# ws2812_clock.net
KiCad netlist of a schematic drawn in EAGLE
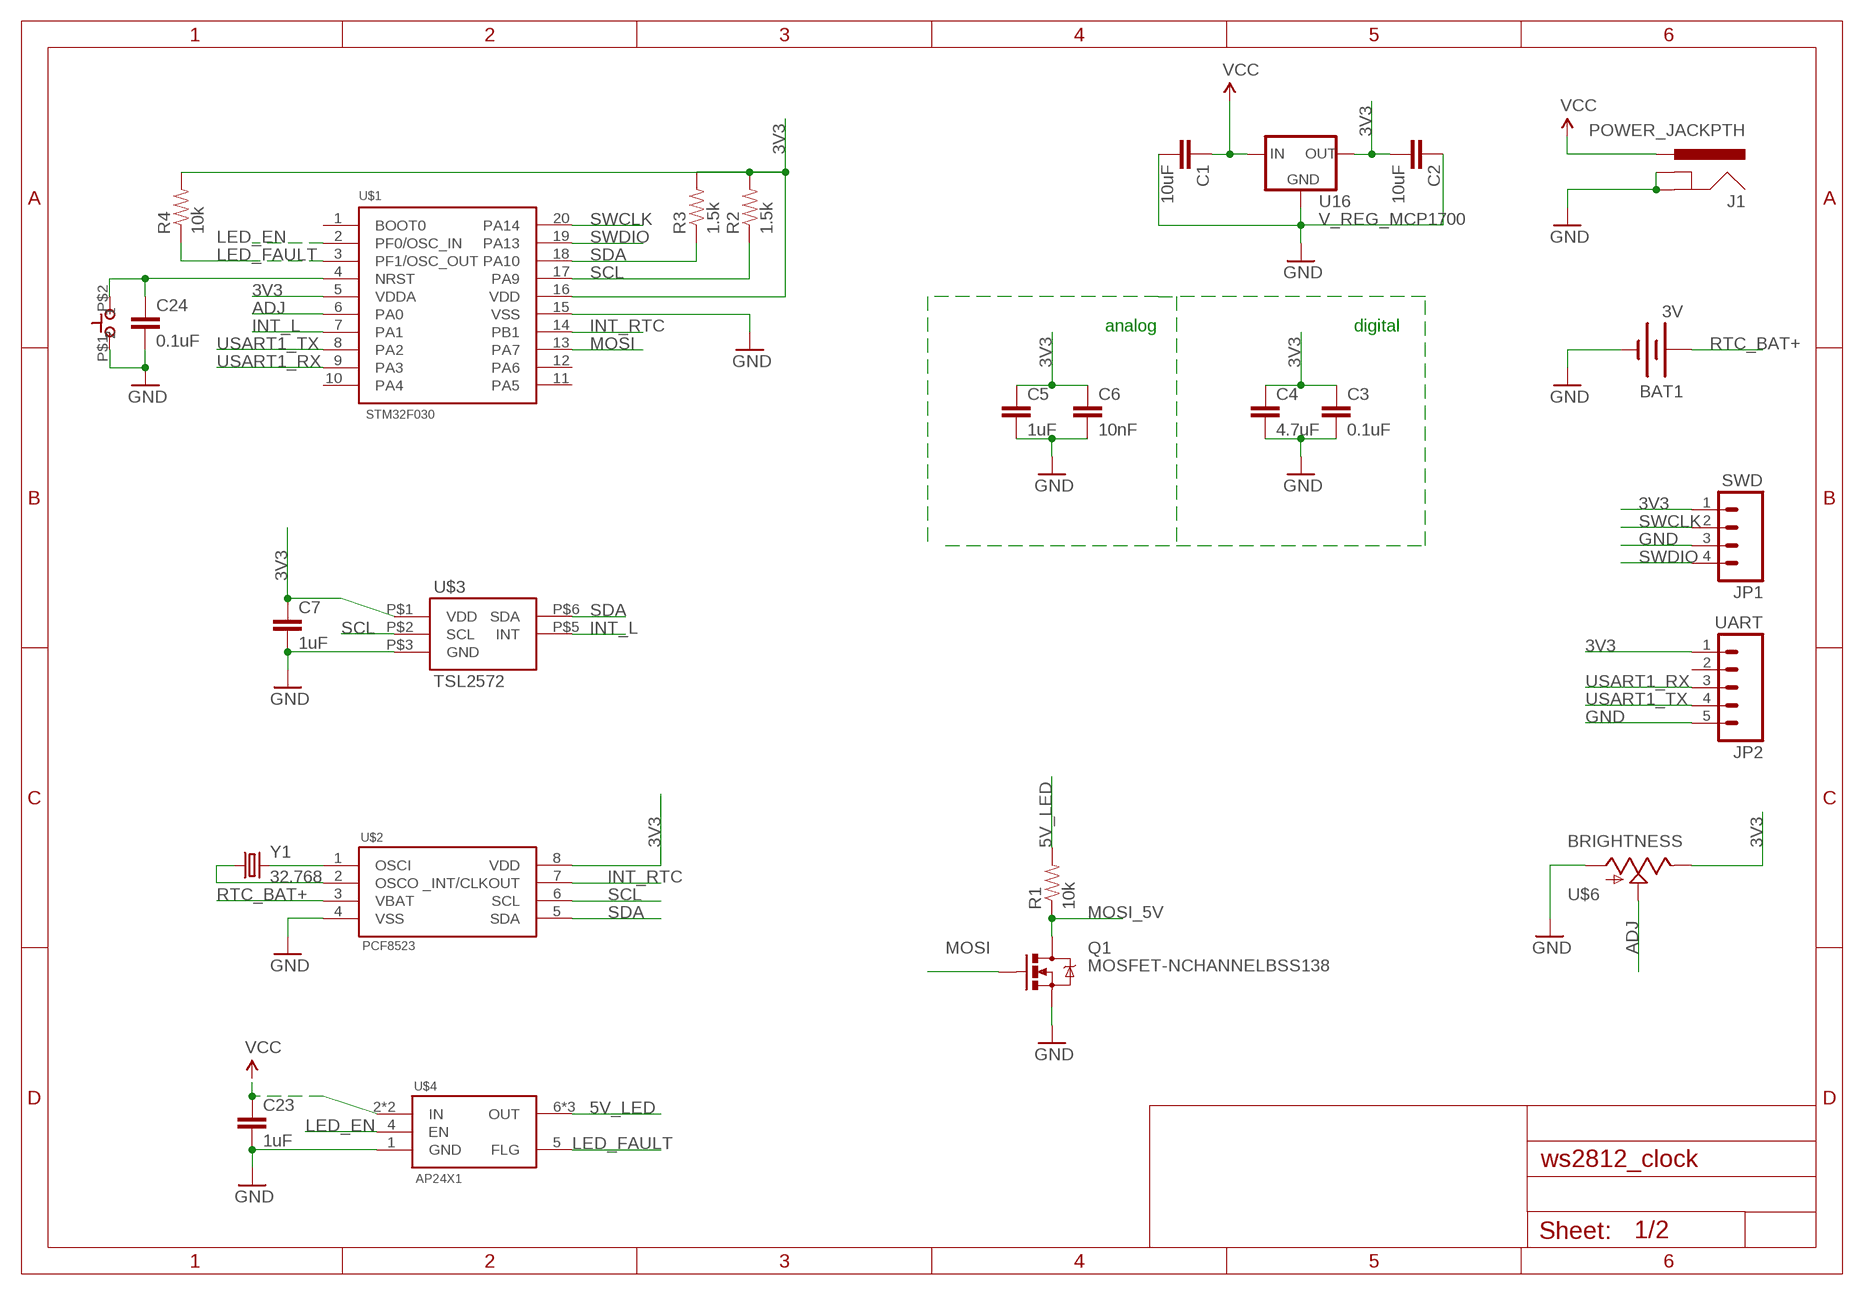
[diagram p0: schematic, sheet 1]
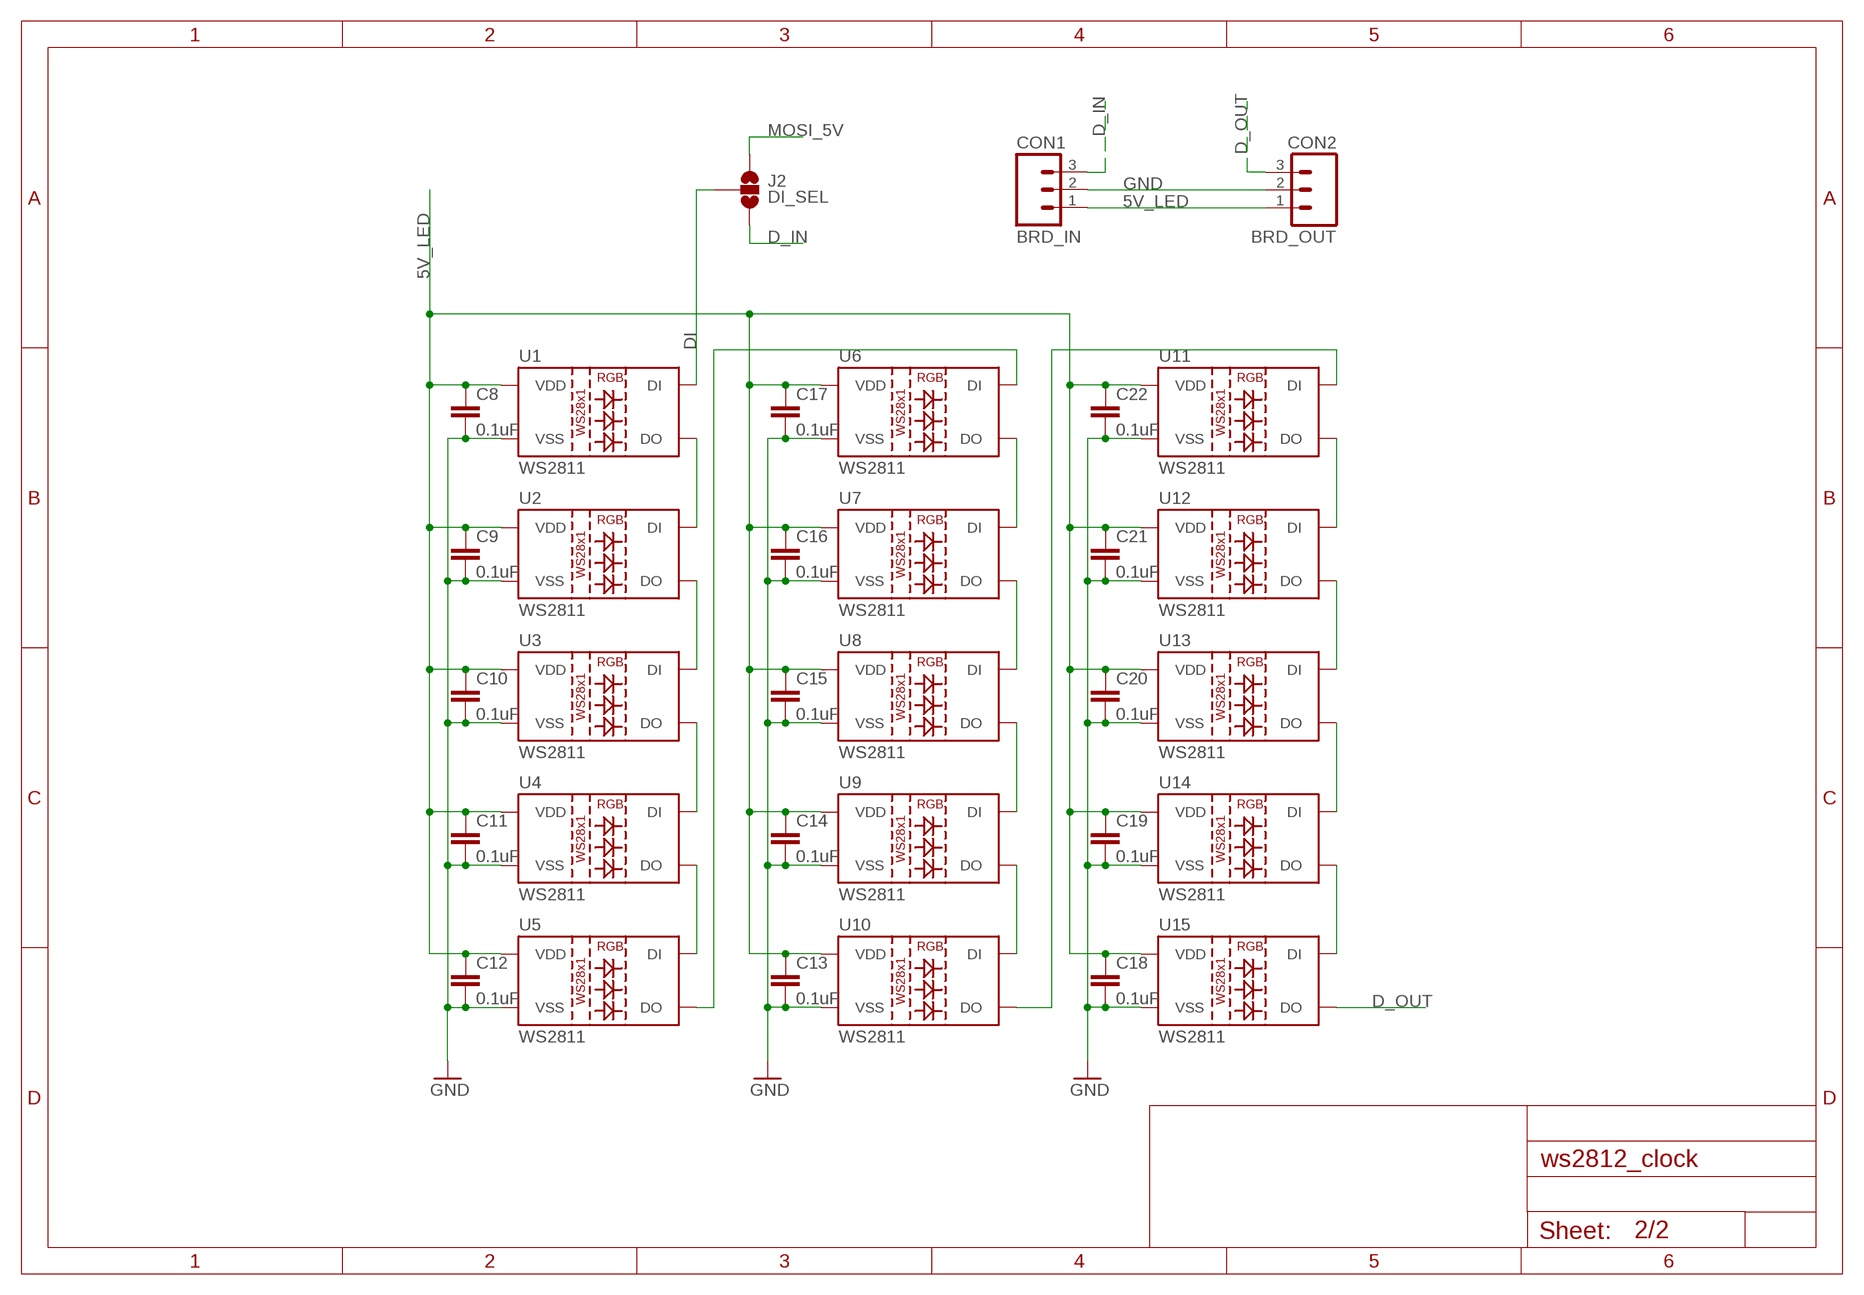
[diagram p1: schematic, sheet 2]

(export (version "E")
  (design (tool "Eeschema 10.0.6"))
  (components
    (comp (ref "C8")
      (value "0.1uF")
      (footprint "eagle-import:0603-CAP")
      (libsource (lib "eagle-import") (part "CAP0603-CAP"))
    )
    (comp (ref "C9")
      (value "0.1uF")
      (footprint "eagle-import:0603-CAP")
      (libsource (lib "eagle-import") (part "CAP0603-CAP"))
    )
    (comp (ref "C10")
      (value "0.1uF")
      (footprint "eagle-import:0603-CAP")
      (libsource (lib "eagle-import") (part "CAP0603-CAP"))
    )
    (comp (ref "C11")
      (value "0.1uF")
      (footprint "eagle-import:0603-CAP")
      (libsource (lib "eagle-import") (part "CAP0603-CAP"))
    )
    (comp (ref "C12")
      (value "0.1uF")
      (footprint "eagle-import:0603-CAP")
      (libsource (lib "eagle-import") (part "CAP0603-CAP"))
    )
    (comp (ref "C13")
      (value "0.1uF")
      (footprint "eagle-import:0603-CAP")
      (libsource (lib "eagle-import") (part "CAP0603-CAP"))
    )
    (comp (ref "C14")
      (value "0.1uF")
      (footprint "eagle-import:0603-CAP")
      (libsource (lib "eagle-import") (part "CAP0603-CAP"))
    )
    (comp (ref "C15")
      (value "0.1uF")
      (footprint "eagle-import:0603-CAP")
      (libsource (lib "eagle-import") (part "CAP0603-CAP"))
    )
    (comp (ref "C16")
      (value "0.1uF")
      (footprint "eagle-import:0603-CAP")
      (libsource (lib "eagle-import") (part "CAP0603-CAP"))
    )
    (comp (ref "C17")
      (value "0.1uF")
      (footprint "eagle-import:0603-CAP")
      (libsource (lib "eagle-import") (part "CAP0603-CAP"))
    )
    (comp (ref "C18")
      (value "0.1uF")
      (footprint "eagle-import:0603-CAP")
      (libsource (lib "eagle-import") (part "CAP0603-CAP"))
    )
    (comp (ref "C19")
      (value "0.1uF")
      (footprint "eagle-import:0603-CAP")
      (libsource (lib "eagle-import") (part "CAP0603-CAP"))
    )
    (comp (ref "C20")
      (value "0.1uF")
      (footprint "eagle-import:0603-CAP")
      (libsource (lib "eagle-import") (part "CAP0603-CAP"))
    )
    (comp (ref "C21")
      (value "0.1uF")
      (footprint "eagle-import:0603-CAP")
      (libsource (lib "eagle-import") (part "CAP0603-CAP"))
    )
    (comp (ref "C22")
      (value "0.1uF")
      (footprint "eagle-import:0603-CAP")
      (libsource (lib "eagle-import") (part "CAP0603-CAP"))
    )
    (comp (ref "CON1")
      (value "BRD_IN")
      (footprint "eagle-import:1X03")
      (libsource (lib "eagle-import") (part "M03PTH"))
    )
    (comp (ref "CON2")
      (value "BRD_OUT")
      (footprint "eagle-import:1X03")
      (libsource (lib "eagle-import") (part "M03PTH"))
    )
    (comp (ref "J2")
      (value "DI_SEL")
      (footprint "eagle-import:SJ_2")
      (libsource (lib "eagle-import") (part "SOLDERJUMPER_2WAYT"))
    )
    (comp (ref "U1")
      (value "WS2811")
      (footprint "eagle-import:LED-TRICOLOR-5050-IC")
      (libsource (lib "eagle-import") (part "LED-TRICOLOR-5050-ICWS2811"))
    )
    (comp (ref "U2")
      (value "WS2811")
      (footprint "eagle-import:LED-TRICOLOR-5050-IC")
      (libsource (lib "eagle-import") (part "LED-TRICOLOR-5050-ICWS2811"))
    )
    (comp (ref "U3")
      (value "WS2811")
      (footprint "eagle-import:LED-TRICOLOR-5050-IC")
      (libsource (lib "eagle-import") (part "LED-TRICOLOR-5050-ICWS2811"))
    )
    (comp (ref "U4")
      (value "WS2811")
      (footprint "eagle-import:LED-TRICOLOR-5050-IC")
      (libsource (lib "eagle-import") (part "LED-TRICOLOR-5050-ICWS2811"))
    )
    (comp (ref "U5")
      (value "WS2811")
      (footprint "eagle-import:LED-TRICOLOR-5050-IC")
      (libsource (lib "eagle-import") (part "LED-TRICOLOR-5050-ICWS2811"))
    )
    (comp (ref "U6")
      (value "WS2811")
      (footprint "eagle-import:LED-TRICOLOR-5050-IC")
      (libsource (lib "eagle-import") (part "LED-TRICOLOR-5050-ICWS2811"))
    )
    (comp (ref "U7")
      (value "WS2811")
      (footprint "eagle-import:LED-TRICOLOR-5050-IC")
      (libsource (lib "eagle-import") (part "LED-TRICOLOR-5050-ICWS2811"))
    )
    (comp (ref "U8")
      (value "WS2811")
      (footprint "eagle-import:LED-TRICOLOR-5050-IC")
      (libsource (lib "eagle-import") (part "LED-TRICOLOR-5050-ICWS2811"))
    )
    (comp (ref "U9")
      (value "WS2811")
      (footprint "eagle-import:LED-TRICOLOR-5050-IC")
      (libsource (lib "eagle-import") (part "LED-TRICOLOR-5050-ICWS2811"))
    )
    (comp (ref "U10")
      (value "WS2811")
      (footprint "eagle-import:LED-TRICOLOR-5050-IC")
      (libsource (lib "eagle-import") (part "LED-TRICOLOR-5050-ICWS2811"))
    )
    (comp (ref "U11")
      (value "WS2811")
      (footprint "eagle-import:LED-TRICOLOR-5050-IC")
      (libsource (lib "eagle-import") (part "LED-TRICOLOR-5050-ICWS2811"))
    )
    (comp (ref "U12")
      (value "WS2811")
      (footprint "eagle-import:LED-TRICOLOR-5050-IC")
      (libsource (lib "eagle-import") (part "LED-TRICOLOR-5050-ICWS2811"))
    )
    (comp (ref "U13")
      (value "WS2811")
      (footprint "eagle-import:LED-TRICOLOR-5050-IC")
      (libsource (lib "eagle-import") (part "LED-TRICOLOR-5050-ICWS2811"))
    )
    (comp (ref "U14")
      (value "WS2811")
      (footprint "eagle-import:LED-TRICOLOR-5050-IC")
      (libsource (lib "eagle-import") (part "LED-TRICOLOR-5050-ICWS2811"))
    )
    (comp (ref "U15")
      (value "WS2811")
      (footprint "eagle-import:LED-TRICOLOR-5050-IC")
      (libsource (lib "eagle-import") (part "LED-TRICOLOR-5050-ICWS2811"))
    )
    (comp (ref "BAT1")
      (value "3V")
      (footprint "eagle-import:BATTCON_12MM_PTH")
      (libsource (lib "eagle-import") (part "BATTERY12PTH"))
    )
    (comp (ref "C1")
      (value "10uF")
      (footprint "eagle-import:0805")
      (libsource (lib "eagle-import") (part "CAP0805"))
    )
    (comp (ref "C2")
      (value "10uF")
      (footprint "eagle-import:0805")
      (libsource (lib "eagle-import") (part "CAP0805"))
    )
    (comp (ref "C3")
      (value "0.1uF")
      (footprint "eagle-import:0603-CAP")
      (libsource (lib "eagle-import") (part "CAP0603-CAP"))
    )
    (comp (ref "C4")
      (value "4.7uF")
      (footprint "eagle-import:0805")
      (libsource (lib "eagle-import") (part "CAP0805"))
    )
    (comp (ref "C5")
      (value "1uF")
      (footprint "eagle-import:0805")
      (libsource (lib "eagle-import") (part "CAP0805"))
    )
    (comp (ref "C6")
      (value "10nF")
      (footprint "eagle-import:0603-CAP")
      (libsource (lib "eagle-import") (part "CAP0603-CAP"))
    )
    (comp (ref "C7")
      (value "1uF")
      (footprint "eagle-import:0805")
      (libsource (lib "eagle-import") (part "CAP0805"))
    )
    (comp (ref "C23")
      (value "1uF")
      (footprint "eagle-import:0805")
      (libsource (lib "eagle-import") (part "CAP0805"))
    )
    (comp (ref "C24")
      (value "0.1uF")
      (footprint "eagle-import:0603-CAP")
      (libsource (lib "eagle-import") (part "CAP0603-CAP"))
    )
    (comp (ref "J1")
      (value "POWER_JACKPTH")
      (footprint "eagle-import:POWER_JACK_PTH")
      (libsource (lib "eagle-import") (part "POWER_JACKPTH"))
    )
    (comp (ref "JP1")
      (value "SWD")
      (footprint "eagle-import:1X04")
      (libsource (lib "eagle-import") (part "M04PTH"))
    )
    (comp (ref "JP2")
      (value "UART")
      (footprint "eagle-import:1X05")
      (libsource (lib "eagle-import") (part "M05PTH"))
    )
    (comp (ref "Q1")
      (value "MOSFET-NCHANNELBSS138")
      (footprint "eagle-import:SOT23")
      (libsource (lib "eagle-import") (part "MOSFET-NCHANNELBSS138"))
    )
    (comp (ref "R1")
      (value "10k")
      (footprint "eagle-import:0603-RES")
      (libsource (lib "eagle-import") (part "RESISTOR0603-RES"))
    )
    (comp (ref "R2")
      (value "1.5k")
      (footprint "eagle-import:0603-RES")
      (libsource (lib "eagle-import") (part "RESISTOR0603-RES"))
    )
    (comp (ref "R3")
      (value "1.5k")
      (footprint "eagle-import:0603-RES")
      (libsource (lib "eagle-import") (part "RESISTOR0603-RES"))
    )
    (comp (ref "R4")
      (value "10k")
      (footprint "eagle-import:0603-RES")
      (libsource (lib "eagle-import") (part "RESISTOR0603-RES"))
    )
    (comp (ref "U$1")
      (value "STM32F030")
      (footprint "eagle-import:TSSOP20")
      (libsource (lib "eagle-import") (part "STM32F030"))
    )
    (comp (ref "U$2")
      (value "PCF8523")
      (footprint "eagle-import:SO08")
      (libsource (lib "eagle-import") (part "PCF8523"))
    )
    (comp (ref "U$3")
      (value "TSL2572")
      (footprint "eagle-import:FN-6")
      (libsource (lib "eagle-import") (part "TSL2572"))
    )
    (comp (ref "U$4")
      (value "AP24X1")
      (footprint "eagle-import:MSOP8")
      (libsource (lib "eagle-import") (part "AP24X1"))
    )
    (comp (ref "U$5")
      (value "TACTILE-SWITCH")
      (footprint "eagle-import:6X3.5")
      (libsource (lib "eagle-import") (part "TACTILE-SWITCH"))
    )
    (comp (ref "U$6")
      (value "BRIGHTNESS")
      (footprint "eagle-import:TRIM_POT")
      (libsource (lib "eagle-import") (part "POTTRIM"))
    )
    (comp (ref "U16")
      (value "V_REG_MCP1700")
      (footprint "eagle-import:SOT23-3")
      (libsource (lib "eagle-import") (part "V_REG_MCP1700"))
    )
    (comp (ref "Y1")
      (value "32.768")
      (footprint "eagle-import:CRYSTAL-CITIZEN")
      (libsource (lib "eagle-import") (part "CRYSTALCITIZEN"))
    )
  )
  (nets
    (net (code "1") (name "3V3") (class "Default")
      (node (ref "C2") (pin "2") (pinfunction "2_2") (pintype "passive"))
      (node (ref "C3") (pin "1") (pinfunction "1_1") (pintype "passive"))
      (node (ref "C4") (pin "1") (pinfunction "1_1") (pintype "passive"))
      (node (ref "C5") (pin "1") (pinfunction "1_1") (pintype "passive"))
      (node (ref "C6") (pin "1") (pinfunction "1_1") (pintype "passive"))
      (node (ref "C7") (pin "1") (pinfunction "1_1") (pintype "passive"))
      (node (ref "JP1") (pin "1") (pinfunction "1_1") (pintype "passive"))
      (node (ref "JP2") (pin "1") (pinfunction "1_1") (pintype "passive"))
      (node (ref "R2") (pin "2") (pinfunction "2_2") (pintype "passive"))
      (node (ref "R3") (pin "2") (pinfunction "2_2") (pintype "passive"))
      (node (ref "R4") (pin "2") (pinfunction "2_2") (pintype "passive"))
      (node (ref "U$1") (pin "16") (pinfunction "VDD_16") (pintype "bidirectional"))
      (node (ref "U$1") (pin "5") (pinfunction "VDDA_5") (pintype "bidirectional"))
      (node (ref "U$2") (pin "8") (pinfunction "VDD_8") (pintype "bidirectional"))
      (node (ref "U$3") (pin "P$1") (pinfunction "VDD_P$1") (pintype "bidirectional"))
      (node (ref "U$6") (pin "2") (pinfunction "E_2") (pintype "passive"))
      (node (ref "U16") (pin "2") (pinfunction "OUT_2") (pintype "output"))
    )
    (net (code "2") (name "5V_LED") (class "Default")
      (node (ref "C10") (pin "1") (pinfunction "1_1") (pintype "passive"))
      (node (ref "C11") (pin "1") (pinfunction "1_1") (pintype "passive"))
      (node (ref "C12") (pin "1") (pinfunction "1_1") (pintype "passive"))
      (node (ref "C13") (pin "1") (pinfunction "1_1") (pintype "passive"))
      (node (ref "C14") (pin "1") (pinfunction "1_1") (pintype "passive"))
      (node (ref "C15") (pin "1") (pinfunction "1_1") (pintype "passive"))
      (node (ref "C16") (pin "1") (pinfunction "1_1") (pintype "passive"))
      (node (ref "C17") (pin "1") (pinfunction "1_1") (pintype "passive"))
      (node (ref "C18") (pin "1") (pinfunction "1_1") (pintype "passive"))
      (node (ref "C19") (pin "1") (pinfunction "1_1") (pintype "passive"))
      (node (ref "C20") (pin "1") (pinfunction "1_1") (pintype "passive"))
      (node (ref "C21") (pin "1") (pinfunction "1_1") (pintype "passive"))
      (node (ref "C22") (pin "1") (pinfunction "1_1") (pintype "passive"))
      (node (ref "C8") (pin "1") (pinfunction "1_1") (pintype "passive"))
      (node (ref "C9") (pin "1") (pinfunction "1_1") (pintype "passive"))
      (node (ref "CON1") (pin "1") (pinfunction "1_1") (pintype "passive"))
      (node (ref "CON2") (pin "1") (pinfunction "1_1") (pintype "passive"))
      (node (ref "R1") (pin "2") (pinfunction "2_2") (pintype "passive"))
      (node (ref "U$4") (pin "6") (pinfunction "OUT_6") (pintype "bidirectional"))
      (node (ref "U$4") (pin "7") (pinfunction "OUT_7") (pintype "bidirectional"))
      (node (ref "U$4") (pin "8") (pinfunction "OUT_8") (pintype "bidirectional"))
      (node (ref "U1") (pin "3") (pinfunction "VDD_3") (pintype "bidirectional"))
      (node (ref "U1") (pin "5") (pinfunction "VDD_5") (pintype "bidirectional"))
      (node (ref "U10") (pin "3") (pinfunction "VDD_3") (pintype "bidirectional"))
      (node (ref "U10") (pin "5") (pinfunction "VDD_5") (pintype "bidirectional"))
      (node (ref "U11") (pin "3") (pinfunction "VDD_3") (pintype "bidirectional"))
      (node (ref "U11") (pin "5") (pinfunction "VDD_5") (pintype "bidirectional"))
      (node (ref "U12") (pin "3") (pinfunction "VDD_3") (pintype "bidirectional"))
      (node (ref "U12") (pin "5") (pinfunction "VDD_5") (pintype "bidirectional"))
      (node (ref "U13") (pin "3") (pinfunction "VDD_3") (pintype "bidirectional"))
      (node (ref "U13") (pin "5") (pinfunction "VDD_5") (pintype "bidirectional"))
      (node (ref "U14") (pin "3") (pinfunction "VDD_3") (pintype "bidirectional"))
      (node (ref "U14") (pin "5") (pinfunction "VDD_5") (pintype "bidirectional"))
      (node (ref "U15") (pin "3") (pinfunction "VDD_3") (pintype "bidirectional"))
      (node (ref "U15") (pin "5") (pinfunction "VDD_5") (pintype "bidirectional"))
      (node (ref "U2") (pin "3") (pinfunction "VDD_3") (pintype "bidirectional"))
      (node (ref "U2") (pin "5") (pinfunction "VDD_5") (pintype "bidirectional"))
      (node (ref "U3") (pin "3") (pinfunction "VDD_3") (pintype "bidirectional"))
      (node (ref "U3") (pin "5") (pinfunction "VDD_5") (pintype "bidirectional"))
      (node (ref "U4") (pin "3") (pinfunction "VDD_3") (pintype "bidirectional"))
      (node (ref "U4") (pin "5") (pinfunction "VDD_5") (pintype "bidirectional"))
      (node (ref "U5") (pin "3") (pinfunction "VDD_3") (pintype "bidirectional"))
      (node (ref "U5") (pin "5") (pinfunction "VDD_5") (pintype "bidirectional"))
      (node (ref "U6") (pin "3") (pinfunction "VDD_3") (pintype "bidirectional"))
      (node (ref "U6") (pin "5") (pinfunction "VDD_5") (pintype "bidirectional"))
      (node (ref "U7") (pin "3") (pinfunction "VDD_3") (pintype "bidirectional"))
      (node (ref "U7") (pin "5") (pinfunction "VDD_5") (pintype "bidirectional"))
      (node (ref "U8") (pin "3") (pinfunction "VDD_3") (pintype "bidirectional"))
      (node (ref "U8") (pin "5") (pinfunction "VDD_5") (pintype "bidirectional"))
      (node (ref "U9") (pin "3") (pinfunction "VDD_3") (pintype "bidirectional"))
      (node (ref "U9") (pin "5") (pinfunction "VDD_5") (pintype "bidirectional"))
    )
    (net (code "3") (name "ADJ") (class "Default")
      (node (ref "U$1") (pin "6") (pinfunction "PA0_6") (pintype "bidirectional"))
      (node (ref "U$6") (pin "1") (pinfunction "S_1") (pintype "passive"))
    )
    (net (code "4") (name "DI") (class "Default")
      (node (ref "J2") (pin "2") (pinfunction "2_2") (pintype "passive"))
      (node (ref "U1") (pin "2") (pinfunction "DI_2") (pintype "bidirectional"))
    )
    (net (code "5") (name "D_IN") (class "Default")
      (node (ref "CON1") (pin "3") (pinfunction "3_3") (pintype "passive"))
      (node (ref "J2") (pin "3") (pinfunction "3_3") (pintype "passive"))
    )
    (net (code "6") (name "D_OUT") (class "Default")
      (node (ref "CON2") (pin "3") (pinfunction "3_3") (pintype "passive"))
      (node (ref "U15") (pin "1") (pinfunction "DO_1") (pintype "bidirectional"))
    )
    (net (code "7") (name "GND") (class "Default")
      (node (ref "BAT1") (pin "GND") (pinfunction "-_GND") (pintype "power_in"))
      (node (ref "C1") (pin "2") (pinfunction "2_2") (pintype "passive"))
      (node (ref "C10") (pin "2") (pinfunction "2_2") (pintype "passive"))
      (node (ref "C11") (pin "2") (pinfunction "2_2") (pintype "passive"))
      (node (ref "C12") (pin "2") (pinfunction "2_2") (pintype "passive"))
      (node (ref "C13") (pin "2") (pinfunction "2_2") (pintype "passive"))
      (node (ref "C14") (pin "2") (pinfunction "2_2") (pintype "passive"))
      (node (ref "C15") (pin "2") (pinfunction "2_2") (pintype "passive"))
      (node (ref "C16") (pin "2") (pinfunction "2_2") (pintype "passive"))
      (node (ref "C17") (pin "2") (pinfunction "2_2") (pintype "passive"))
      (node (ref "C18") (pin "2") (pinfunction "2_2") (pintype "passive"))
      (node (ref "C19") (pin "2") (pinfunction "2_2") (pintype "passive"))
      (node (ref "C2") (pin "1") (pinfunction "1_1") (pintype "passive"))
      (node (ref "C20") (pin "2") (pinfunction "2_2") (pintype "passive"))
      (node (ref "C21") (pin "2") (pinfunction "2_2") (pintype "passive"))
      (node (ref "C22") (pin "2") (pinfunction "2_2") (pintype "passive"))
      (node (ref "C23") (pin "2") (pinfunction "2_2") (pintype "passive"))
      (node (ref "C24") (pin "2") (pinfunction "2_2") (pintype "passive"))
      (node (ref "C3") (pin "2") (pinfunction "2_2") (pintype "passive"))
      (node (ref "C4") (pin "2") (pinfunction "2_2") (pintype "passive"))
      (node (ref "C5") (pin "2") (pinfunction "2_2") (pintype "passive"))
      (node (ref "C6") (pin "2") (pinfunction "2_2") (pintype "passive"))
      (node (ref "C7") (pin "2") (pinfunction "2_2") (pintype "passive"))
      (node (ref "C8") (pin "2") (pinfunction "2_2") (pintype "passive"))
      (node (ref "C9") (pin "2") (pinfunction "2_2") (pintype "passive"))
      (node (ref "CON1") (pin "2") (pinfunction "2_2") (pintype "passive"))
      (node (ref "CON2") (pin "2") (pinfunction "2_2") (pintype "passive"))
      (node (ref "J1") (pin "GND") (pinfunction "GND_GND") (pintype "bidirectional"))
      (node (ref "J1") (pin "GNDBREAK") (pinfunction "GNDBREAK_GNDBREAK") (pintype "bidirectional"))
      (node (ref "JP1") (pin "3") (pinfunction "3_3") (pintype "passive"))
      (node (ref "JP2") (pin "5") (pinfunction "5_5") (pintype "passive"))
      (node (ref "Q1") (pin "2") (pinfunction "S_2") (pintype "passive"))
      (node (ref "U$1") (pin "15") (pinfunction "VSS_15") (pintype "bidirectional"))
      (node (ref "U$2") (pin "4") (pinfunction "VSS_4") (pintype "bidirectional"))
      (node (ref "U$3") (pin "P$3") (pinfunction "GND_P$3") (pintype "bidirectional"))
      (node (ref "U$4") (pin "1") (pinfunction "GND_1") (pintype "bidirectional"))
      (node (ref "U$5") (pin "P$1") (pinfunction "1_P$1") (pintype "bidirectional"))
      (node (ref "U$6") (pin "3") (pinfunction "A_3") (pintype "passive"))
      (node (ref "U1") (pin "6") (pinfunction "VSS_6") (pintype "bidirectional"))
      (node (ref "U10") (pin "6") (pinfunction "VSS_6") (pintype "bidirectional"))
      (node (ref "U11") (pin "6") (pinfunction "VSS_6") (pintype "bidirectional"))
      (node (ref "U12") (pin "6") (pinfunction "VSS_6") (pintype "bidirectional"))
      (node (ref "U13") (pin "6") (pinfunction "VSS_6") (pintype "bidirectional"))
      (node (ref "U14") (pin "6") (pinfunction "VSS_6") (pintype "bidirectional"))
      (node (ref "U15") (pin "6") (pinfunction "VSS_6") (pintype "bidirectional"))
      (node (ref "U16") (pin "1") (pinfunction "GND_1") (pintype "input"))
      (node (ref "U2") (pin "6") (pinfunction "VSS_6") (pintype "bidirectional"))
      (node (ref "U3") (pin "6") (pinfunction "VSS_6") (pintype "bidirectional"))
      (node (ref "U4") (pin "6") (pinfunction "VSS_6") (pintype "bidirectional"))
      (node (ref "U5") (pin "6") (pinfunction "VSS_6") (pintype "bidirectional"))
      (node (ref "U6") (pin "6") (pinfunction "VSS_6") (pintype "bidirectional"))
      (node (ref "U7") (pin "6") (pinfunction "VSS_6") (pintype "bidirectional"))
      (node (ref "U8") (pin "6") (pinfunction "VSS_6") (pintype "bidirectional"))
      (node (ref "U9") (pin "6") (pinfunction "VSS_6") (pintype "bidirectional"))
    )
    (net (code "8") (name "INT_L") (class "Default")
      (node (ref "U$1") (pin "7") (pinfunction "PA1_7") (pintype "bidirectional"))
      (node (ref "U$3") (pin "P$5") (pinfunction "INT_P$5") (pintype "bidirectional"))
    )
    (net (code "9") (name "INT_RTC") (class "Default")
      (node (ref "U$1") (pin "14") (pinfunction "PB1_14") (pintype "bidirectional"))
      (node (ref "U$2") (pin "7") (pinfunction "_INT/CLKOUT_7") (pintype "bidirectional"))
    )
    (net (code "10") (name "LED_EN") (class "Default")
      (node (ref "U$1") (pin "2") (pinfunction "PF0/OSC_IN_2") (pintype "bidirectional"))
      (node (ref "U$4") (pin "4") (pinfunction "EN_4") (pintype "bidirectional"))
    )
    (net (code "11") (name "LED_FAULT") (class "Default")
      (node (ref "R4") (pin "1") (pinfunction "1_1") (pintype "passive"))
      (node (ref "U$1") (pin "3") (pinfunction "PF1/OSC_OUT_3") (pintype "bidirectional"))
      (node (ref "U$4") (pin "5") (pinfunction "FLG_5") (pintype "bidirectional"))
    )
    (net (code "12") (name "MOSI") (class "Default")
      (node (ref "Q1") (pin "1") (pinfunction "G_1") (pintype "passive"))
      (node (ref "U$1") (pin "13") (pinfunction "PA7_13") (pintype "bidirectional"))
    )
    (net (code "13") (name "MOSI_5V") (class "Default")
      (node (ref "J2") (pin "1") (pinfunction "1_1") (pintype "passive"))
      (node (ref "Q1") (pin "3") (pinfunction "D_3") (pintype "passive"))
      (node (ref "R1") (pin "1") (pinfunction "1_1") (pintype "passive"))
    )
    (net (code "14") (name "Net-(U$1-NRST)") (class "Default")
      (node (ref "C24") (pin "1") (pinfunction "1_1") (pintype "passive"))
      (node (ref "U$1") (pin "4") (pinfunction "NRST_4") (pintype "bidirectional"))
      (node (ref "U$5") (pin "P$2") (pinfunction "2_P$2") (pintype "bidirectional"))
    )
    (net (code "15") (name "Net-(U$2-OSCI)") (class "Default")
      (node (ref "U$2") (pin "1") (pinfunction "OSCI_1") (pintype "bidirectional"))
      (node (ref "Y1") (pin "P$2") (pinfunction "2_P$2") (pintype "passive"))
    )
    (net (code "16") (name "Net-(U$2-OSCO)") (class "Default")
      (node (ref "U$2") (pin "2") (pinfunction "OSCO_2") (pintype "bidirectional"))
      (node (ref "Y1") (pin "P$1") (pinfunction "1_P$1") (pintype "passive"))
    )
    (net (code "17") (name "Net-(U1-DO)") (class "Default")
      (node (ref "U1") (pin "1") (pinfunction "DO_1") (pintype "bidirectional"))
      (node (ref "U2") (pin "2") (pinfunction "DI_2") (pintype "bidirectional"))
    )
    (net (code "18") (name "Net-(U2-DO)") (class "Default")
      (node (ref "U2") (pin "1") (pinfunction "DO_1") (pintype "bidirectional"))
      (node (ref "U3") (pin "2") (pinfunction "DI_2") (pintype "bidirectional"))
    )
    (net (code "19") (name "Net-(U3-DO)") (class "Default")
      (node (ref "U3") (pin "1") (pinfunction "DO_1") (pintype "bidirectional"))
      (node (ref "U4") (pin "2") (pinfunction "DI_2") (pintype "bidirectional"))
    )
    (net (code "20") (name "Net-(U4-DO)") (class "Default")
      (node (ref "U4") (pin "1") (pinfunction "DO_1") (pintype "bidirectional"))
      (node (ref "U5") (pin "2") (pinfunction "DI_2") (pintype "bidirectional"))
    )
    (net (code "21") (name "Net-(U5-DO)") (class "Default")
      (node (ref "U5") (pin "1") (pinfunction "DO_1") (pintype "bidirectional"))
      (node (ref "U6") (pin "2") (pinfunction "DI_2") (pintype "bidirectional"))
    )
    (net (code "22") (name "Net-(U6-DO)") (class "Default")
      (node (ref "U6") (pin "1") (pinfunction "DO_1") (pintype "bidirectional"))
      (node (ref "U7") (pin "2") (pinfunction "DI_2") (pintype "bidirectional"))
    )
    (net (code "23") (name "Net-(U7-DO)") (class "Default")
      (node (ref "U7") (pin "1") (pinfunction "DO_1") (pintype "bidirectional"))
      (node (ref "U8") (pin "2") (pinfunction "DI_2") (pintype "bidirectional"))
    )
    (net (code "24") (name "Net-(U8-DO)") (class "Default")
      (node (ref "U8") (pin "1") (pinfunction "DO_1") (pintype "bidirectional"))
      (node (ref "U9") (pin "2") (pinfunction "DI_2") (pintype "bidirectional"))
    )
    (net (code "25") (name "Net-(U10-DI)") (class "Default")
      (node (ref "U10") (pin "2") (pinfunction "DI_2") (pintype "bidirectional"))
      (node (ref "U9") (pin "1") (pinfunction "DO_1") (pintype "bidirectional"))
    )
    (net (code "26") (name "Net-(U10-DO)") (class "Default")
      (node (ref "U10") (pin "1") (pinfunction "DO_1") (pintype "bidirectional"))
      (node (ref "U11") (pin "2") (pinfunction "DI_2") (pintype "bidirectional"))
    )
    (net (code "27") (name "Net-(U11-DO)") (class "Default")
      (node (ref "U11") (pin "1") (pinfunction "DO_1") (pintype "bidirectional"))
      (node (ref "U12") (pin "2") (pinfunction "DI_2") (pintype "bidirectional"))
    )
    (net (code "28") (name "Net-(U12-DO)") (class "Default")
      (node (ref "U12") (pin "1") (pinfunction "DO_1") (pintype "bidirectional"))
      (node (ref "U13") (pin "2") (pinfunction "DI_2") (pintype "bidirectional"))
    )
    (net (code "29") (name "Net-(U13-DO)") (class "Default")
      (node (ref "U13") (pin "1") (pinfunction "DO_1") (pintype "bidirectional"))
      (node (ref "U14") (pin "2") (pinfunction "DI_2") (pintype "bidirectional"))
    )
    (net (code "30") (name "Net-(U14-DO)") (class "Default")
      (node (ref "U14") (pin "1") (pinfunction "DO_1") (pintype "bidirectional"))
      (node (ref "U15") (pin "2") (pinfunction "DI_2") (pintype "bidirectional"))
    )
    (net (code "31") (name "RTC_BAT+") (class "Default")
      (node (ref "BAT1") (pin "VCC@1") (pinfunction "+_VCC@1") (pintype "power_in"))
      (node (ref "U$2") (pin "3") (pinfunction "VBAT_3") (pintype "bidirectional"))
    )
    (net (code "32") (name "SCL") (class "Default")
      (node (ref "R2") (pin "1") (pinfunction "1_1") (pintype "passive"))
      (node (ref "U$1") (pin "17") (pinfunction "PA9_17") (pintype "bidirectional"))
      (node (ref "U$2") (pin "6") (pinfunction "SCL_6") (pintype "bidirectional"))
      (node (ref "U$3") (pin "P$2") (pinfunction "SCL_P$2") (pintype "bidirectional"))
    )
    (net (code "33") (name "SDA") (class "Default")
      (node (ref "R3") (pin "1") (pinfunction "1_1") (pintype "passive"))
      (node (ref "U$1") (pin "18") (pinfunction "PA10_18") (pintype "bidirectional"))
      (node (ref "U$2") (pin "5") (pinfunction "SDA_5") (pintype "bidirectional"))
      (node (ref "U$3") (pin "P$6") (pinfunction "SDA_P$6") (pintype "bidirectional"))
    )
    (net (code "34") (name "SWCLK") (class "Default")
      (node (ref "JP1") (pin "2") (pinfunction "2_2") (pintype "passive"))
      (node (ref "U$1") (pin "20") (pinfunction "PA14_20") (pintype "bidirectional"))
    )
    (net (code "35") (name "SWDIO") (class "Default")
      (node (ref "JP1") (pin "4") (pinfunction "4_4") (pintype "passive"))
      (node (ref "U$1") (pin "19") (pinfunction "PA13_19") (pintype "bidirectional"))
    )
    (net (code "36") (name "USART1_RX") (class "Default")
      (node (ref "JP2") (pin "3") (pinfunction "3_3") (pintype "passive"))
      (node (ref "U$1") (pin "9") (pinfunction "PA3_9") (pintype "bidirectional"))
    )
    (net (code "37") (name "USART1_TX") (class "Default")
      (node (ref "JP2") (pin "4") (pinfunction "4_4") (pintype "passive"))
      (node (ref "U$1") (pin "8") (pinfunction "PA2_8") (pintype "bidirectional"))
    )
    (net (code "38") (name "VCC") (class "Default")
      (node (ref "C1") (pin "1") (pinfunction "1_1") (pintype "passive"))
      (node (ref "C23") (pin "1") (pinfunction "1_1") (pintype "passive"))
      (node (ref "J1") (pin "PWR") (pinfunction "PWR_PWR") (pintype "bidirectional"))
      (node (ref "U$4") (pin "2") (pinfunction "IN_2") (pintype "bidirectional"))
      (node (ref "U$4") (pin "3") (pinfunction "IN_3") (pintype "bidirectional"))
      (node (ref "U16") (pin "3") (pinfunction "IN_3") (pintype "input"))
    )
    (net (code "39") (name "unconnected-(JP2-Pad2)") (class "Default")
      (node (ref "JP2") (pin "2") (pinfunction "2_2") (pintype "passive"))
    )
    (net (code "40") (name "unconnected-(U$1-BOOT0-Pad1)") (class "Default")
      (node (ref "U$1") (pin "1") (pinfunction "BOOT0_1") (pintype "bidirectional"))
    )
    (net (code "41") (name "unconnected-(U$1-PA4-Pad10)") (class "Default")
      (node (ref "U$1") (pin "10") (pinfunction "PA4_10") (pintype "bidirectional"))
    )
    (net (code "42") (name "unconnected-(U$1-PA5-Pad11)") (class "Default")
      (node (ref "U$1") (pin "11") (pinfunction "PA5_11") (pintype "bidirectional"))
    )
    (net (code "43") (name "unconnected-(U$1-PA6-Pad12)") (class "Default")
      (node (ref "U$1") (pin "12") (pinfunction "PA6_12") (pintype "bidirectional"))
    )
  )
)
